# Sheet1.net
KiCad netlist of a schematic drawn in Altium Designer
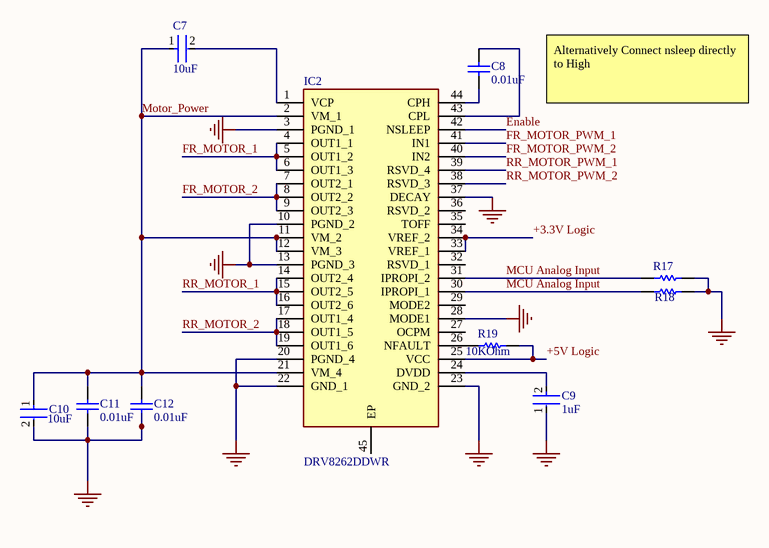
[diagram p0: Sheet1.SchDoc]

(export (version "E")
  (design (tool "Eeschema 10.0.6"))
  (components
    (comp (ref "C7")
      (value "GRM32ER71H106KA12L")
      (footprint "FP-GRM32-MFG")
      (description "CAP CER 10UF 50V X7R 1210")
      (fields
        (field (name "TOLERANCE") "10%")
        (field (name "MANUFACTURER") "Murata")
        (field (name "CAPACITANCE") "10uF")
      )
      (libsource (lib "Altium Content Vault") (part "11868f565c42a9108669ba33697ecf6"))
    )
    (comp (ref "C8")
      (value "VJ0603Y103MXXAC")
      (footprint "CAPC1608X92X38NL15T08")
      (fields (field (name "MANUFACTURER") "Vitramon") (field (name "CAPACITANCE") "0.01uF"))
      (libsource (lib "Altium Content Vault") (part "CAP"))
    )
    (comp (ref "C9")
      (value "GRM188R60J105KA01D")
      (footprint "FP-GRM188-0_1-MFG")
      (description "CAP CER 1UF 6.3V X5R 0603")
      (fields
        (field (name "CAPACITANCE") "1uF")
        (field (name "TOLERANCE") "10%")
        (field (name "VOLTAGE") "6.3V")
      )
      (libsource (lib "Altium Content Vault") (part "236180d848d6139a670b325ea6854c9"))
    )
    (comp (ref "C10")
      (value "GRM32ER71H106KA12L")
      (footprint "FP-GRM32-MFG")
      (description "CAP CER 10UF 50V X7R 1210")
      (fields
        (field (name "TOLERANCE") "10%")
        (field (name "MANUFACTURER") "Murata")
        (field (name "CAPACITANCE") "10uF")
      )
      (libsource (lib "Altium Content Vault") (part "11868f565c42a9108669ba33697ecf6"))
    )
    (comp (ref "C11")
      (value "VJ0603Y103MXXAC")
      (footprint "CAPC1608X92X38NL15T08")
      (fields (field (name "MANUFACTURER") "Vitramon") (field (name "CAPACITANCE") "0.01uF"))
      (libsource (lib "Altium Content Vault") (part "CAP"))
    )
    (comp (ref "C12")
      (value "VJ0603Y103MXXAC")
      (footprint "CAPC1608X92X38NL15T08")
      (fields (field (name "MANUFACTURER") "Vitramon") (field (name "CAPACITANCE") "0.01uF"))
      (libsource (lib "Altium Content Vault") (part "CAP"))
    )
    (comp (ref "IC2")
      (value "DRV8262DDWR")
      (footprint "SOP64P810X120-45N")
      (description "Integrated Circuit")
      (fields (field (name "MOUSER PART NUMBER") "595-DRV8262DDWR"))
      (libsource (lib "SamacSys") (part "DRV8262DDWR"))
    )
    (comp (ref "R17")
      (value "ERJ-3EKF2611V")
      (footprint "RESC1608X55X30NL15T15")
      (fields (field (name "MANUFACTURER") "Panasonic"))
      (libsource (lib "Altium Content Vault") (part "RES"))
    )
    (comp (ref "R18")
      (value "ERJ-3EKF2611V")
      (footprint "RESC1608X55X30NL15T15")
      (fields (field (name "MANUFACTURER") "Panasonic"))
      (libsource (lib "Altium Content Vault") (part "RES"))
    )
    (comp (ref "R19")
      (value "ERJ3EKF1002V")
      (footprint "RESC1609X55X30LL15T15")
      (description "Chip Resistor, 10 KOhm, +/- 1%, 0.1 W, -55 to 155 degC, 0603 (1608 Metric), RoHS, Tape and Reel")
      (fields
        (field (name "RESISTANCE") "10KOhm")
        (field (name "TOLERANCE") "1%")
        (field (name "MANUFACTURER") "Panasonic")
      )
      (libsource (lib "Altium Content Vault") (part "RES-2"))
    )
  )
  (nets
    (net (code "1") (name "/+3.3V Logic") (class "Default")
      (node (ref "IC2") (pin "33") (pinfunction "VREF_1_33") (pintype "passive"))
      (node (ref "IC2") (pin "34") (pinfunction "VREF_2_34") (pintype "passive"))
    )
    (net (code "2") (name "/+5V Logic") (class "Default")
      (node (ref "IC2") (pin "25") (pinfunction "VCC_25") (pintype "passive"))
      (node (ref "R19") (pin "2") (pinfunction "2_2") (pintype "passive"))
    )
    (net (code "3") (name "/Enable") (class "Default")
      (node (ref "IC2") (pin "42") (pinfunction "NSLEEP_42") (pintype "passive"))
    )
    (net (code "4") (name "/FR_MOTOR_1") (class "Default")
      (node (ref "IC2") (pin "4") (pinfunction "OUT1_1_4") (pintype "passive"))
      (node (ref "IC2") (pin "5") (pinfunction "OUT1_2_5") (pintype "passive"))
      (node (ref "IC2") (pin "6") (pinfunction "OUT1_3_6") (pintype "passive"))
    )
    (net (code "5") (name "/FR_MOTOR_2") (class "Default")
      (node (ref "IC2") (pin "7") (pinfunction "OUT2_1_7") (pintype "passive"))
      (node (ref "IC2") (pin "8") (pinfunction "OUT2_2_8") (pintype "passive"))
      (node (ref "IC2") (pin "9") (pinfunction "OUT2_3_9") (pintype "passive"))
    )
    (net (code "6") (name "/FR_MOTOR_PWM_1") (class "Default")
      (node (ref "IC2") (pin "41") (pinfunction "IN1_41") (pintype "passive"))
    )
    (net (code "7") (name "/FR_MOTOR_PWM_2") (class "Default")
      (node (ref "IC2") (pin "40") (pinfunction "IN2_40") (pintype "passive"))
    )
    (net (code "8") (name "/MCU Analog Input") (class "Default")
      (node (ref "IC2") (pin "30") (pinfunction "IPROPI_1_30") (pintype "passive"))
      (node (ref "IC2") (pin "31") (pinfunction "IPROPI_2_31") (pintype "passive"))
      (node (ref "R17") (pin "1") (pinfunction "1_1") (pintype "passive"))
      (node (ref "R18") (pin "1") (pinfunction "1_1") (pintype "passive"))
    )
    (net (code "9") (name "/Motor_Power") (class "Default")
      (node (ref "C10") (pin "1") (pinfunction "1_1") (pintype "passive"))
      (node (ref "C11") (pin "2") (pinfunction "2_2") (pintype "passive"))
      (node (ref "C12") (pin "2") (pinfunction "2_2") (pintype "passive"))
      (node (ref "C7") (pin "1") (pinfunction "1_1") (pintype "passive"))
      (node (ref "IC2") (pin "11") (pinfunction "VM_2_11") (pintype "passive"))
      (node (ref "IC2") (pin "12") (pinfunction "VM_3_12") (pintype "passive"))
      (node (ref "IC2") (pin "2") (pinfunction "VM_1_2") (pintype "passive"))
      (node (ref "IC2") (pin "21") (pinfunction "VM_4_21") (pintype "passive"))
    )
    (net (code "10") (name "/RR_MOTOR_1") (class "Default")
      (node (ref "IC2") (pin "14") (pinfunction "OUT2_4_14") (pintype "passive"))
      (node (ref "IC2") (pin "15") (pinfunction "OUT2_5_15") (pintype "passive"))
      (node (ref "IC2") (pin "16") (pinfunction "OUT2_6_16") (pintype "passive"))
    )
    (net (code "11") (name "/RR_MOTOR_2") (class "Default")
      (node (ref "IC2") (pin "17") (pinfunction "OUT1_4_17") (pintype "passive"))
      (node (ref "IC2") (pin "18") (pinfunction "OUT1_5_18") (pintype "passive"))
      (node (ref "IC2") (pin "19") (pinfunction "OUT1_6_19") (pintype "passive"))
    )
    (net (code "12") (name "/RR_MOTOR_PWM_1") (class "Default")
      (node (ref "IC2") (pin "39") (pinfunction "RSVD_4_39") (pintype "passive"))
    )
    (net (code "13") (name "/RR_MOTOR_PWM_2") (class "Default")
      (node (ref "IC2") (pin "38") (pinfunction "RSVD_3_38") (pintype "passive"))
    )
    (net (code "14") (name "GND") (class "Default")
      (node (ref "C10") (pin "2") (pinfunction "2_2") (pintype "passive"))
      (node (ref "C11") (pin "1") (pinfunction "1_1") (pintype "passive"))
      (node (ref "C12") (pin "1") (pinfunction "1_1") (pintype "passive"))
      (node (ref "C9") (pin "1") (pinfunction "1_1") (pintype "passive"))
      (node (ref "IC2") (pin "10") (pinfunction "PGND_2_10") (pintype "passive"))
      (node (ref "IC2") (pin "13") (pinfunction "PGND_3_13") (pintype "passive"))
      (node (ref "IC2") (pin "20") (pinfunction "PGND_4_20") (pintype "passive"))
      (node (ref "IC2") (pin "22") (pinfunction "GND_1_22") (pintype "passive"))
      (node (ref "IC2") (pin "23") (pinfunction "GND_2_23") (pintype "passive"))
      (node (ref "IC2") (pin "28") (pinfunction "MODE1_28") (pintype "passive"))
      (node (ref "IC2") (pin "3") (pinfunction "PGND_1_3") (pintype "passive"))
      (node (ref "IC2") (pin "37") (pinfunction "DECAY_37") (pintype "passive"))
      (node (ref "R17") (pin "2") (pinfunction "2_2") (pintype "passive"))
      (node (ref "R18") (pin "2") (pinfunction "2_2") (pintype "passive"))
    )
    (net (code "15") (name "Net-(IC2-CPH)") (class "Default")
      (node (ref "C8") (pin "1") (pinfunction "1_1") (pintype "passive"))
      (node (ref "IC2") (pin "44") (pinfunction "CPH_44") (pintype "passive"))
    )
    (net (code "16") (name "Net-(IC2-CPL)") (class "Default")
      (node (ref "C8") (pin "2") (pinfunction "2_2") (pintype "passive"))
      (node (ref "IC2") (pin "43") (pinfunction "CPL_43") (pintype "passive"))
    )
    (net (code "17") (name "Net-(IC2-DVDD)") (class "Default")
      (node (ref "C9") (pin "2") (pinfunction "2_2") (pintype "passive"))
      (node (ref "IC2") (pin "24") (pinfunction "DVDD_24") (pintype "passive"))
    )
    (net (code "18") (name "Net-(IC2-NFAULT)") (class "Default")
      (node (ref "IC2") (pin "26") (pinfunction "NFAULT_26") (pintype "passive"))
      (node (ref "R19") (pin "1") (pinfunction "1_1") (pintype "passive"))
    )
    (net (code "19") (name "Net-(IC2-VCP)") (class "Default")
      (node (ref "C7") (pin "2") (pinfunction "2_2") (pintype "passive"))
      (node (ref "IC2") (pin "1") (pinfunction "VCP_1") (pintype "passive"))
    )
    (net (code "20") (name "unconnected-(IC2-EP-Pad45)") (class "Default")
      (node (ref "IC2") (pin "45") (pinfunction "EP_45") (pintype "passive"))
    )
    (net (code "21") (name "unconnected-(IC2-MODE2-Pad29)") (class "Default")
      (node (ref "IC2") (pin "29") (pinfunction "MODE2_29") (pintype "passive"))
    )
    (net (code "22") (name "unconnected-(IC2-OCPM-Pad27)") (class "Default")
      (node (ref "IC2") (pin "27") (pinfunction "OCPM_27") (pintype "passive"))
    )
    (net (code "23") (name "unconnected-(IC2-RSVD_1-Pad32)") (class "Default")
      (node (ref "IC2") (pin "32") (pinfunction "RSVD_1_32") (pintype "passive"))
    )
    (net (code "24") (name "unconnected-(IC2-RSVD_2-Pad36)") (class "Default")
      (node (ref "IC2") (pin "36") (pinfunction "RSVD_2_36") (pintype "passive"))
    )
    (net (code "25") (name "unconnected-(IC2-TOFF-Pad35)") (class "Default")
      (node (ref "IC2") (pin "35") (pinfunction "TOFF_35") (pintype "passive"))
    )
  )
)
